# schematic_2.net
KiCad netlist of a schematic drawn in EAGLE
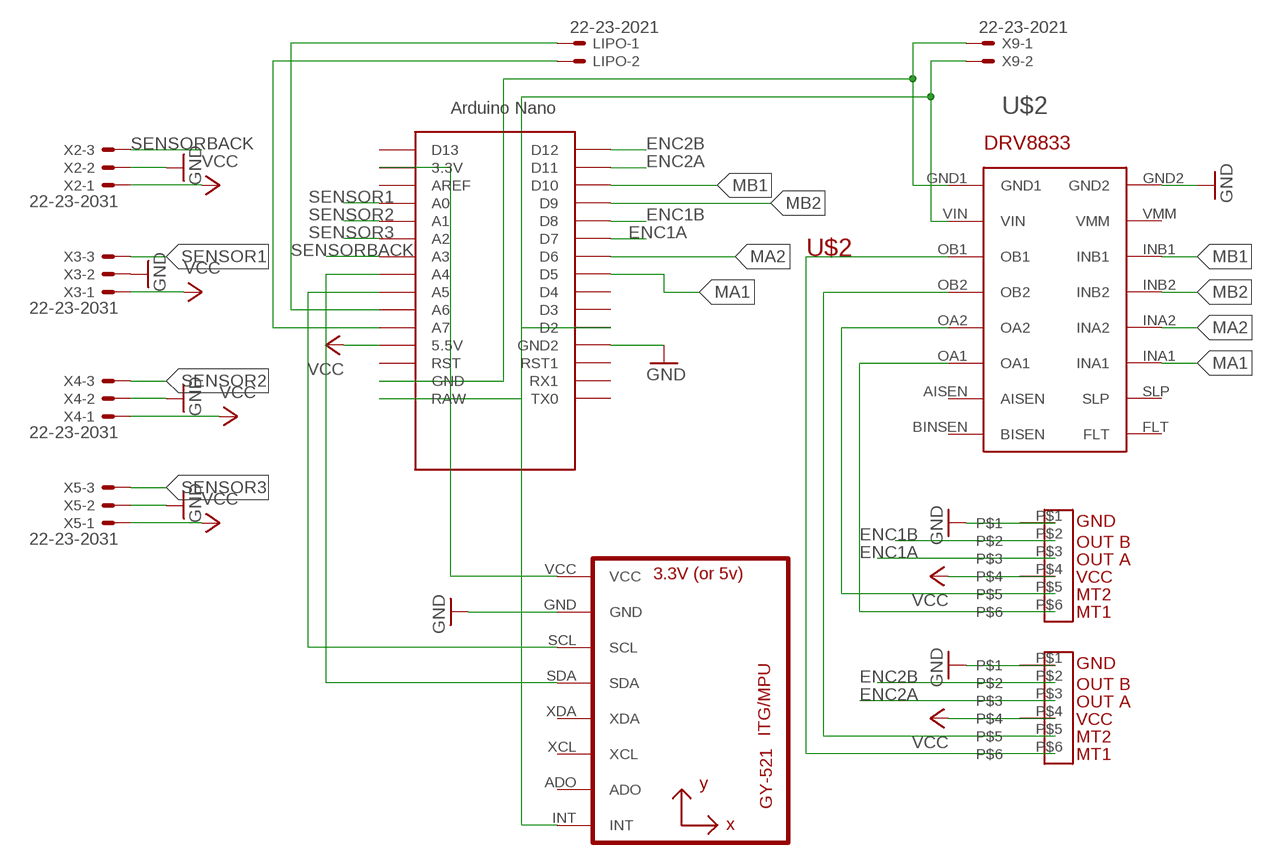
[diagram p0: schematic, sheet 1]

(export (version "E")
  (design (tool "Eeschema 10.0.6"))
  (components
    (comp (ref "LIPO")
      (value "22-23-2021")
      (footprint "eagle-import:22-23-2021")
      (fields (field (name "MF") "MOLEX"))
      (libsource (lib "eagle-import") (part "22-23-2021"))
    )
    (comp (ref "U$1")
      (value "NANO")
      (footprint "eagle-import:NANO")
      (libsource (lib "eagle-import") (part "NANO"))
    )
    (comp (ref "U$2")
      (value "POLOLU-DRV8833")
      (footprint "eagle-import:POLOLU-DRV8833")
      (libsource (lib "eagle-import") (part "POLOLU-DRV8833"))
    )
    (comp (ref "U$3")
      (value "PINHEADER")
      (footprint "eagle-import:PINHEADER")
      (libsource (lib "eagle-import") (part "PINHEADER"))
    )
    (comp (ref "U$4")
      (value "PINHEADER")
      (footprint "eagle-import:PINHEADER")
      (libsource (lib "eagle-import") (part "PINHEADER"))
    )
    (comp (ref "U1")
      (value "GY-521MPU6050")
      (footprint "eagle-import:GY-521")
      (libsource (lib "eagle-import") (part "GY-521MPU6050"))
    )
    (comp (ref "X2")
      (value "22-23-2031")
      (footprint "eagle-import:22-23-2031")
      (fields (field (name "MF") "MOLEX"))
      (libsource (lib "eagle-import") (part "22-23-2031"))
    )
    (comp (ref "X3")
      (value "22-23-2031")
      (footprint "eagle-import:22-23-2031")
      (fields (field (name "MF") "MOLEX"))
      (libsource (lib "eagle-import") (part "22-23-2031"))
    )
    (comp (ref "X4")
      (value "22-23-2031")
      (footprint "eagle-import:22-23-2031")
      (fields (field (name "MF") "MOLEX"))
      (libsource (lib "eagle-import") (part "22-23-2031"))
    )
    (comp (ref "X5")
      (value "22-23-2031")
      (footprint "eagle-import:22-23-2031")
      (fields (field (name "MF") "MOLEX"))
      (libsource (lib "eagle-import") (part "22-23-2031"))
    )
    (comp (ref "X9")
      (value "22-23-2021")
      (footprint "eagle-import:22-23-2021")
      (fields (field (name "MF") "MOLEX"))
      (libsource (lib "eagle-import") (part "22-23-2021"))
    )
  )
  (nets
    (net (code "1") (name "/ENC1A") (class "Default")
      (node (ref "U$1") (pin "D7") (pinfunction "D7_D7") (pintype "bidirectional"))
      (node (ref "U$3") (pin "P$3") (pinfunction "P$3_P$3") (pintype "bidirectional"))
    )
    (net (code "2") (name "/ENC1B") (class "Default")
      (node (ref "U$1") (pin "D8") (pinfunction "D8_D8") (pintype "bidirectional"))
      (node (ref "U$3") (pin "P$2") (pinfunction "P$2_P$2") (pintype "bidirectional"))
    )
    (net (code "3") (name "/ENC2A") (class "Default")
      (node (ref "U$1") (pin "D11") (pinfunction "D11_D11") (pintype "bidirectional"))
      (node (ref "U$4") (pin "P$3") (pinfunction "P$3_P$3") (pintype "bidirectional"))
    )
    (net (code "4") (name "/ENC2B") (class "Default")
      (node (ref "U$1") (pin "D12") (pinfunction "D12_D12") (pintype "bidirectional"))
      (node (ref "U$4") (pin "P$2") (pinfunction "P$2_P$2") (pintype "bidirectional"))
    )
    (net (code "5") (name "/SENSORBACK") (class "Default")
      (node (ref "U$1") (pin "A3") (pinfunction "A3_A3") (pintype "bidirectional"))
      (node (ref "X2") (pin "3") (pinfunction "S_3") (pintype "passive"))
    )
    (net (code "6") (name "GND") (class "Default")
      (node (ref "U$1") (pin "GND1") (pinfunction "GND2_GND1") (pintype "bidirectional"))
      (node (ref "U$2") (pin "GND2") (pinfunction "GND2_GND2") (pintype "bidirectional"))
      (node (ref "U$3") (pin "P$1") (pinfunction "P$1_P$1") (pintype "bidirectional"))
      (node (ref "U$4") (pin "P$1") (pinfunction "P$1_P$1") (pintype "bidirectional"))
      (node (ref "U1") (pin "GND") (pinfunction "GND_GND") (pintype "bidirectional"))
      (node (ref "X2") (pin "2") (pinfunction "S_2") (pintype "passive"))
      (node (ref "X3") (pin "2") (pinfunction "S_2") (pintype "passive"))
      (node (ref "X4") (pin "2") (pinfunction "S_2") (pintype "passive"))
      (node (ref "X5") (pin "2") (pinfunction "S_2") (pintype "passive"))
    )
    (net (code "7") (name "MA1") (class "Default")
      (node (ref "U$1") (pin "D5") (pinfunction "D5_D5") (pintype "bidirectional"))
      (node (ref "U$2") (pin "INA1") (pinfunction "INA1_INA1") (pintype "bidirectional"))
    )
    (net (code "8") (name "MA2") (class "Default")
      (node (ref "U$1") (pin "D6") (pinfunction "D6_D6") (pintype "bidirectional"))
      (node (ref "U$2") (pin "INA2") (pinfunction "INA2_INA2") (pintype "bidirectional"))
    )
    (net (code "9") (name "MB1") (class "Default")
      (node (ref "U$1") (pin "D10") (pinfunction "D10_D10") (pintype "bidirectional"))
      (node (ref "U$2") (pin "INB1") (pinfunction "INB1_INB1") (pintype "bidirectional"))
    )
    (net (code "10") (name "MB2") (class "Default")
      (node (ref "U$1") (pin "D9") (pinfunction "D9_D9") (pintype "bidirectional"))
      (node (ref "U$2") (pin "INB2") (pinfunction "INB2_INB2") (pintype "bidirectional"))
    )
    (net (code "11") (name "Net-(LIPOA-S)") (class "Default")
      (node (ref "LIPO") (pin "1") (pinfunction "S_1") (pintype "passive"))
      (node (ref "U$1") (pin "A6") (pinfunction "A6_A6") (pintype "bidirectional"))
    )
    (net (code "12") (name "Net-(LIPOB-S)") (class "Default")
      (node (ref "LIPO") (pin "2") (pinfunction "S_2") (pintype "passive"))
      (node (ref "U$1") (pin "A7") (pinfunction "A7_A7") (pintype "bidirectional"))
    )
    (net (code "13") (name "Net-(U$1-Pad3.3V)") (class "Default")
      (node (ref "U$1") (pin "3.3V") (pinfunction "3.3V_3.3V") (pintype "bidirectional"))
      (node (ref "U1") (pin "VCC") (pinfunction "VCC_VCC") (pintype "bidirectional"))
    )
    (net (code "14") (name "Net-(U$1-PadA4)") (class "Default")
      (node (ref "U$1") (pin "A4") (pinfunction "A4_A4") (pintype "bidirectional"))
      (node (ref "U1") (pin "SDA") (pinfunction "SDA_SDA") (pintype "bidirectional"))
    )
    (net (code "15") (name "Net-(U$1-PadA5)") (class "Default")
      (node (ref "U$1") (pin "A5") (pinfunction "A5_A5") (pintype "bidirectional"))
      (node (ref "U1") (pin "SCL") (pinfunction "SCL_SCL") (pintype "bidirectional"))
    )
    (net (code "16") (name "Net-(U$1-PadD2)") (class "Default")
      (node (ref "U$1") (pin "D2") (pinfunction "D2_D2") (pintype "bidirectional"))
      (node (ref "U1") (pin "INT") (pinfunction "INT_INT") (pintype "bidirectional"))
    )
    (net (code "17") (name "Net-(U$2-PadOA1)") (class "Default")
      (node (ref "U$2") (pin "OA1") (pinfunction "OA1_OA1") (pintype "bidirectional"))
      (node (ref "U$3") (pin "P$6") (pinfunction "P$6_P$6") (pintype "bidirectional"))
    )
    (net (code "18") (name "Net-(U$2-PadOA2)") (class "Default")
      (node (ref "U$2") (pin "OA2") (pinfunction "OA2_OA2") (pintype "bidirectional"))
      (node (ref "U$3") (pin "P$5") (pinfunction "P$5_P$5") (pintype "bidirectional"))
    )
    (net (code "19") (name "Net-(U$2-PadOB1)") (class "Default")
      (node (ref "U$2") (pin "OB1") (pinfunction "OB1_OB1") (pintype "bidirectional"))
      (node (ref "U$4") (pin "P$6") (pinfunction "P$6_P$6") (pintype "bidirectional"))
    )
    (net (code "20") (name "Net-(U$2-PadOB2)") (class "Default")
      (node (ref "U$2") (pin "OB2") (pinfunction "OB2_OB2") (pintype "bidirectional"))
      (node (ref "U$4") (pin "P$5") (pinfunction "P$5_P$5") (pintype "bidirectional"))
    )
    (net (code "21") (name "Net-(X9A-S)") (class "Default")
      (node (ref "U$1") (pin "GND") (pinfunction "GND_GND") (pintype "bidirectional"))
      (node (ref "U$2") (pin "GND1") (pinfunction "GND1_GND1") (pintype "bidirectional"))
      (node (ref "X9") (pin "1") (pinfunction "S_1") (pintype "passive"))
    )
    (net (code "22") (name "Net-(X9B-S)") (class "Default")
      (node (ref "U$1") (pin "RAW") (pinfunction "RAW_RAW") (pintype "bidirectional"))
      (node (ref "U$2") (pin "VIN") (pinfunction "VIN_VIN") (pintype "bidirectional"))
      (node (ref "X9") (pin "2") (pinfunction "S_2") (pintype "passive"))
    )
    (net (code "23") (name "SENSOR1") (class "Default")
      (node (ref "U$1") (pin "A0") (pinfunction "A0_A0") (pintype "bidirectional"))
      (node (ref "X3") (pin "3") (pinfunction "S_3") (pintype "passive"))
    )
    (net (code "24") (name "SENSOR2") (class "Default")
      (node (ref "U$1") (pin "A1") (pinfunction "A1_A1") (pintype "bidirectional"))
      (node (ref "X4") (pin "3") (pinfunction "S_3") (pintype "passive"))
    )
    (net (code "25") (name "SENSOR3") (class "Default")
      (node (ref "U$1") (pin "A2") (pinfunction "A2_A2") (pintype "bidirectional"))
      (node (ref "X5") (pin "3") (pinfunction "S_3") (pintype "passive"))
    )
    (net (code "26") (name "VCC") (class "Default")
      (node (ref "U$1") (pin "5V") (pinfunction "5.5V_5V") (pintype "bidirectional"))
      (node (ref "U$3") (pin "P$4") (pinfunction "P$4_P$4") (pintype "bidirectional"))
      (node (ref "U$4") (pin "P$4") (pinfunction "P$4_P$4") (pintype "bidirectional"))
      (node (ref "X2") (pin "1") (pinfunction "S_1") (pintype "passive"))
      (node (ref "X3") (pin "1") (pinfunction "S_1") (pintype "passive"))
      (node (ref "X4") (pin "1") (pinfunction "S_1") (pintype "passive"))
      (node (ref "X5") (pin "1") (pinfunction "S_1") (pintype "passive"))
    )
    (net (code "27") (name "unconnected-(U$1-PadAREF)") (class "Default")
      (node (ref "U$1") (pin "AREF") (pinfunction "AREF_AREF") (pintype "bidirectional"))
    )
    (net (code "28") (name "unconnected-(U$1-PadD3)") (class "Default")
      (node (ref "U$1") (pin "D3") (pinfunction "D3_D3") (pintype "bidirectional"))
    )
    (net (code "29") (name "unconnected-(U$1-PadD4)") (class "Default")
      (node (ref "U$1") (pin "D4") (pinfunction "D4_D4") (pintype "bidirectional"))
    )
    (net (code "30") (name "unconnected-(U$1-PadD13)") (class "Default")
      (node (ref "U$1") (pin "D13") (pinfunction "D13_D13") (pintype "bidirectional"))
    )
    (net (code "31") (name "unconnected-(U$1-PadICSP1)") (class "Default")
      (node (ref "U$1") (pin "ICSP1") (pinfunction "ICSP1_ICSP1") (pintype "bidirectional"))
    )
    (net (code "32") (name "unconnected-(U$1-PadICSP2)") (class "Default")
      (node (ref "U$1") (pin "ICSP2") (pinfunction "ICSP2_ICSP2") (pintype "bidirectional"))
    )
    (net (code "33") (name "unconnected-(U$1-PadICSP3)") (class "Default")
      (node (ref "U$1") (pin "ICSP3") (pinfunction "ICSP3_ICSP3") (pintype "bidirectional"))
    )
    (net (code "34") (name "unconnected-(U$1-PadICSP4)") (class "Default")
      (node (ref "U$1") (pin "ICSP4") (pinfunction "ICSP4_ICSP4") (pintype "bidirectional"))
    )
    (net (code "35") (name "unconnected-(U$1-PadICSP5)") (class "Default")
      (node (ref "U$1") (pin "ICSP5") (pinfunction "ICSP5_ICSP5") (pintype "bidirectional"))
    )
    (net (code "36") (name "unconnected-(U$1-PadICSP6)") (class "Default")
      (node (ref "U$1") (pin "ICSP6") (pinfunction "ICSP6_ICSP6") (pintype "bidirectional"))
    )
    (net (code "37") (name "unconnected-(U$1-PadRST)") (class "Default")
      (node (ref "U$1") (pin "RST") (pinfunction "RST_RST") (pintype "bidirectional"))
    )
    (net (code "38") (name "unconnected-(U$1-PadRST1)") (class "Default")
      (node (ref "U$1") (pin "RST1") (pinfunction "RST1_RST1") (pintype "bidirectional"))
    )
    (net (code "39") (name "unconnected-(U$1-PadRX1)") (class "Default")
      (node (ref "U$1") (pin "RX1") (pinfunction "RX1_RX1") (pintype "bidirectional"))
    )
    (net (code "40") (name "unconnected-(U$1-PadTX0)") (class "Default")
      (node (ref "U$1") (pin "TX0") (pinfunction "TX0_TX0") (pintype "bidirectional"))
    )
    (net (code "41") (name "unconnected-(U$2-BISEN-PadBINSEN)") (class "Default")
      (node (ref "U$2") (pin "BINSEN") (pinfunction "BISEN_BINSEN") (pintype "bidirectional"))
    )
    (net (code "42") (name "unconnected-(U$2-PadAISEN)") (class "Default")
      (node (ref "U$2") (pin "AISEN") (pinfunction "AISEN_AISEN") (pintype "bidirectional"))
    )
    (net (code "43") (name "unconnected-(U$2-PadFLT)") (class "Default")
      (node (ref "U$2") (pin "FLT") (pinfunction "FLT_FLT") (pintype "bidirectional"))
    )
    (net (code "44") (name "unconnected-(U$2-PadSLP)") (class "Default")
      (node (ref "U$2") (pin "SLP") (pinfunction "SLP_SLP") (pintype "bidirectional"))
    )
    (net (code "45") (name "unconnected-(U$2-PadVMM)") (class "Default")
      (node (ref "U$2") (pin "VMM") (pinfunction "VMM_VMM") (pintype "output"))
    )
    (net (code "46") (name "unconnected-(U1-PadADO)") (class "Default")
      (node (ref "U1") (pin "ADO") (pinfunction "ADO_ADO") (pintype "bidirectional"))
    )
    (net (code "47") (name "unconnected-(U1-PadXCL)") (class "Default")
      (node (ref "U1") (pin "XCL") (pinfunction "XCL_XCL") (pintype "bidirectional"))
    )
    (net (code "48") (name "unconnected-(U1-PadXDA)") (class "Default")
      (node (ref "U1") (pin "XDA") (pinfunction "XDA_XDA") (pintype "bidirectional"))
    )
  )
)
